# high_pass_hv.net
KiCad netlist of a schematic drawn in EAGLE
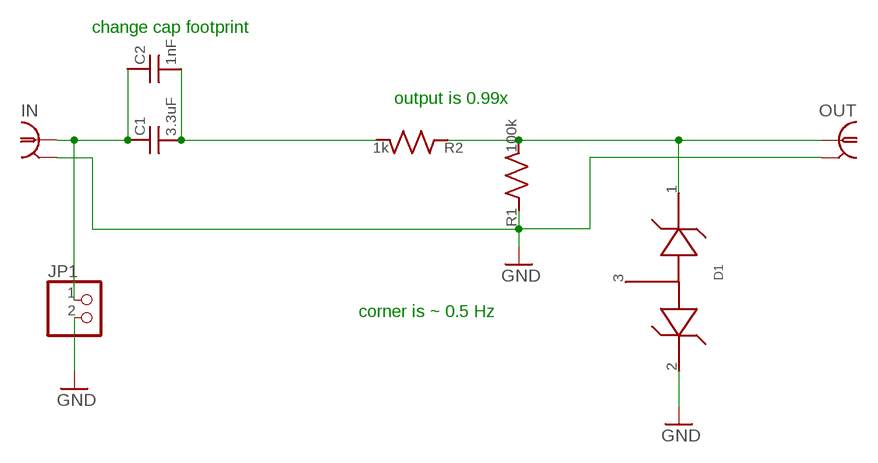
[diagram p0: schematic, sheet 1]

(export (version "E")
  (design (tool "Eeschema 10.0.6"))
  (components
    (comp (ref "C1")
      (value "3.3uF")
      (footprint "eagle-import:CKG-JLEAD")
      (libsource (lib "eagle-import") (part "C_MLCC_SMDCMLCC_JLEAD"))
    )
    (comp (ref "C2")
      (value "1nF")
      (footprint "eagle-import:C_MLCC_1206")
      (libsource (lib "eagle-import") (part "C_MLCC_SMDCMLCC_1206"))
    )
    (comp (ref "D1")
      (value "ZENER-DUAL")
      (footprint "eagle-import:SOT-23")
      (libsource (lib "eagle-import") (part "ZENER-DUAL"))
    )
    (comp (ref "IN")
      (value "BNC-H")
      (footprint "eagle-import:BNC90")
      (libsource (lib "eagle-import") (part "BNC-H"))
    )
    (comp (ref "JP1")
      (value "SCRWTRM-1X2/90_ED550")
      (footprint "eagle-import:1X02_RA_SCRWTRM_ED550")
      (libsource (lib "eagle-import") (part "SCRWTRM-1X2/90_ED550"))
    )
    (comp (ref "OUT")
      (value "BNC-H")
      (footprint "eagle-import:BNC90")
      (libsource (lib "eagle-import") (part "BNC-H"))
    )
    (comp (ref "R1")
      (value "100k")
      (footprint "eagle-import:R_1206")
      (libsource (lib "eagle-import") (part "R_SMDR1206"))
    )
    (comp (ref "R2")
      (value "1k")
      (footprint "eagle-import:R_1206")
      (libsource (lib "eagle-import") (part "R_SMDR1206"))
    )
  )
  (nets
    (net (code "1") (name "GND") (class "Default")
      (node (ref "D1") (pin "2") (pinfunction "P$2_2") (pintype "bidirectional"))
      (node (ref "IN") (pin "2") (pinfunction "2_2") (pintype "passive"))
      (node (ref "JP1") (pin "2") (pinfunction "2_2") (pintype "passive"))
      (node (ref "OUT") (pin "2") (pinfunction "2_2") (pintype "passive"))
      (node (ref "R1") (pin "P$1") (pinfunction "1_P$1") (pintype "passive"))
    )
    (net (code "2") (name "Net-(C1-1)") (class "Default")
      (node (ref "C1") (pin "P$1") (pinfunction "1_P$1") (pintype "passive"))
      (node (ref "C2") (pin "P$1") (pinfunction "1_P$1") (pintype "passive"))
      (node (ref "IN") (pin "1") (pinfunction "1_1") (pintype "passive"))
      (node (ref "JP1") (pin "1") (pinfunction "1_1") (pintype "passive"))
    )
    (net (code "3") (name "Net-(C1-2)") (class "Default")
      (node (ref "C1") (pin "P$2") (pinfunction "2_P$2") (pintype "passive"))
      (node (ref "C2") (pin "P$2") (pinfunction "2_P$2") (pintype "passive"))
      (node (ref "R2") (pin "P$2") (pinfunction "2_P$2") (pintype "passive"))
    )
    (net (code "4") (name "Net-(D1-P$1)") (class "Default")
      (node (ref "D1") (pin "1") (pinfunction "P$1_1") (pintype "bidirectional"))
      (node (ref "OUT") (pin "1") (pinfunction "1_1") (pintype "passive"))
      (node (ref "R1") (pin "P$2") (pinfunction "2_P$2") (pintype "passive"))
      (node (ref "R2") (pin "P$1") (pinfunction "1_P$1") (pintype "passive"))
    )
    (net (code "5") (name "unconnected-(D1-P$3-Pad3)") (class "Default")
      (node (ref "D1") (pin "3") (pinfunction "P$3_3") (pintype "bidirectional"))
    )
  )
)
